# simpleshield.net
KiCad netlist of a schematic drawn in EAGLE
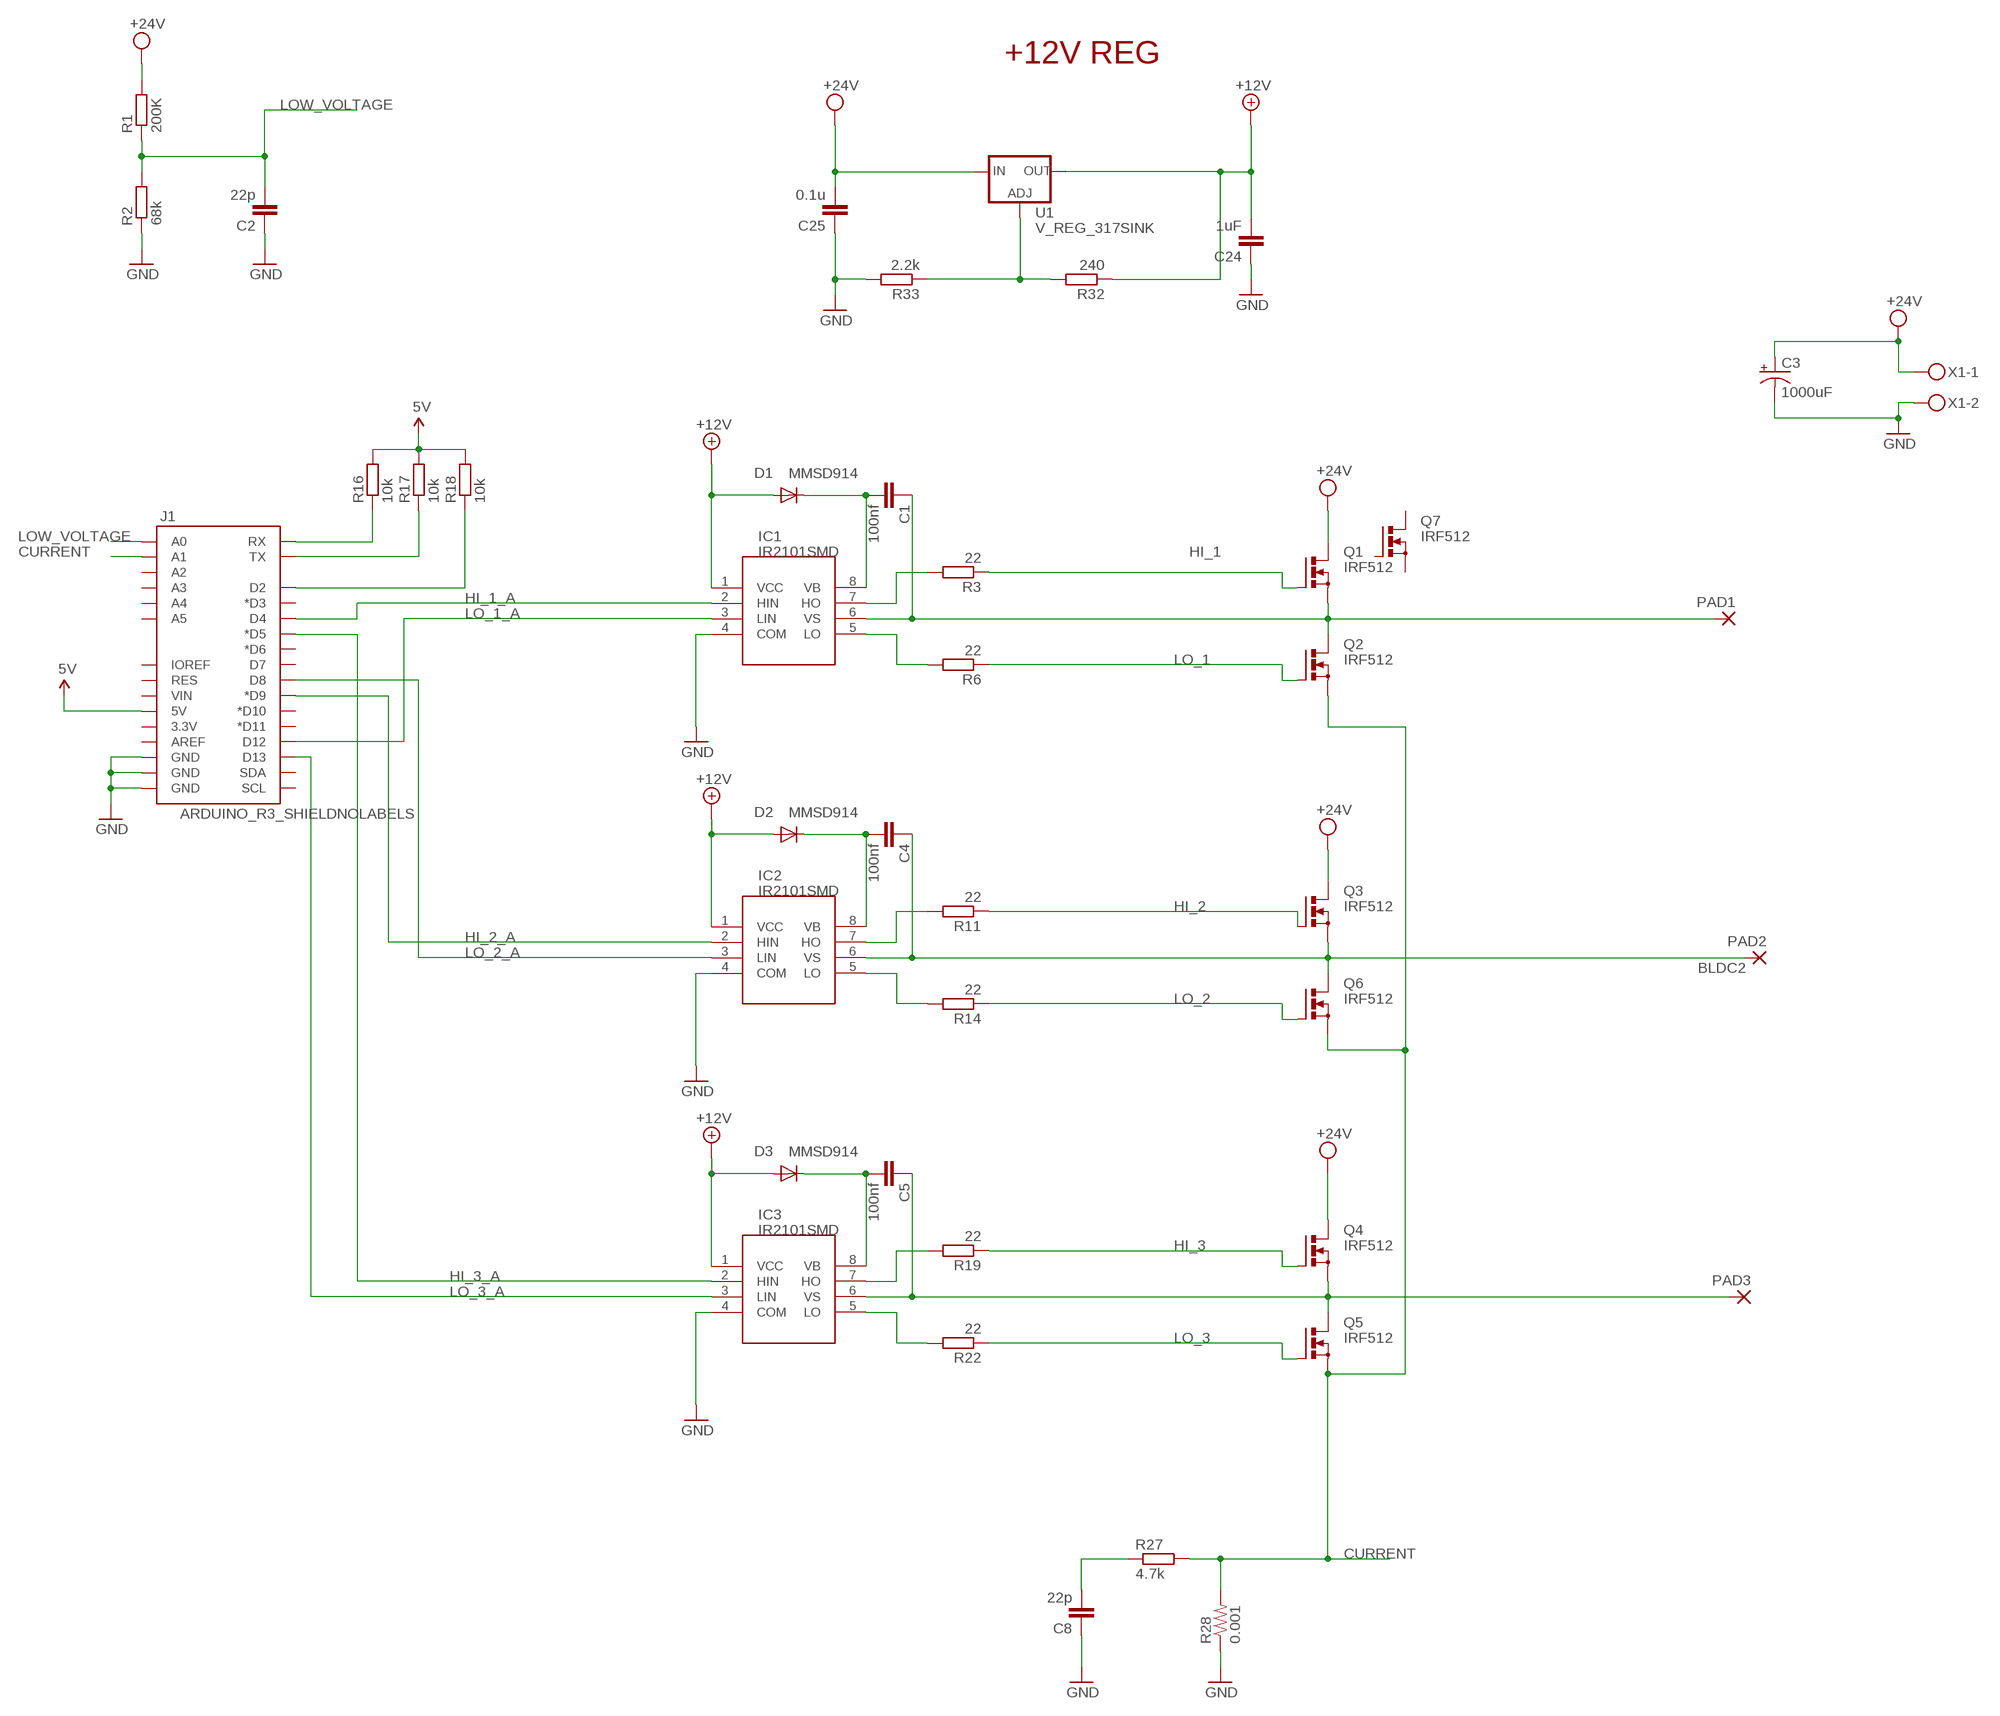
[diagram p0: schematic, sheet 1]

(export (version "E")
  (design (tool "Eeschema 10.0.6"))
  (components
    (comp (ref "C1")
      (value "100nf")
      (footprint "eagle-import:C1206")
      (libsource (lib "eagle-import") (part "C-EUC1206"))
    )
    (comp (ref "C2")
      (value "22p")
      (footprint "eagle-import:C1206")
      (libsource (lib "eagle-import") (part "C-EUC1206"))
    )
    (comp (ref "C3")
      (value "1000uF")
      (footprint "eagle-import:CPOL-RADIAL-1000UF-63V")
      (libsource (lib "eagle-import") (part "CAP_POLPTH3"))
    )
    (comp (ref "C4")
      (value "100nf")
      (footprint "eagle-import:C1206")
      (libsource (lib "eagle-import") (part "C-EUC1206"))
    )
    (comp (ref "C5")
      (value "100nf")
      (footprint "eagle-import:C1206")
      (libsource (lib "eagle-import") (part "C-EUC1206"))
    )
    (comp (ref "C8")
      (value "22p")
      (footprint "eagle-import:C1206")
      (libsource (lib "eagle-import") (part "C-EUC1206"))
    )
    (comp (ref "C24")
      (value "1uF")
      (footprint "eagle-import:C1206")
      (libsource (lib "eagle-import") (part "C-EUC1206"))
    )
    (comp (ref "C25")
      (value "0.1u")
      (footprint "eagle-import:C1206")
      (libsource (lib "eagle-import") (part "C-EUC1206"))
    )
    (comp (ref "D1")
      (value "MMSD914")
      (footprint "eagle-import:SOD123")
      (libsource (lib "eagle-import") (part "DIODE-SOD123"))
    )
    (comp (ref "D2")
      (value "MMSD914")
      (footprint "eagle-import:SOD123")
      (libsource (lib "eagle-import") (part "DIODE-SOD123"))
    )
    (comp (ref "D3")
      (value "MMSD914")
      (footprint "eagle-import:SOD123")
      (libsource (lib "eagle-import") (part "DIODE-SOD123"))
    )
    (comp (ref "IC1")
      (value "IR2101SMD")
      (footprint "eagle-import:SO08")
      (libsource (lib "eagle-import") (part "IR2101SMD"))
    )
    (comp (ref "IC2")
      (value "IR2101SMD")
      (footprint "eagle-import:SO08")
      (libsource (lib "eagle-import") (part "IR2101SMD"))
    )
    (comp (ref "IC3")
      (value "IR2101SMD")
      (footprint "eagle-import:SO08")
      (libsource (lib "eagle-import") (part "IR2101SMD"))
    )
    (comp (ref "J1")
      (value "ARDUINO_R3_SHIELDNOLABELS")
      (footprint "eagle-import:UNO_R3_SHIELD_NOLABELS")
      (libsource (lib "eagle-import") (part "ARDUINO_R3_SHIELDNOLABELS"))
    )
    (comp (ref "PAD1")
      (value "3,81/1,4")
      (footprint "eagle-import:3,81_1,4")
      (libsource (lib "eagle-import") (part "3,81/1,4"))
    )
    (comp (ref "PAD2")
      (value "3,81/1,4")
      (footprint "eagle-import:3,81_1,4")
      (libsource (lib "eagle-import") (part "3,81/1,4"))
    )
    (comp (ref "PAD3")
      (value "3,81/1,4")
      (footprint "eagle-import:3,81_1,4")
      (libsource (lib "eagle-import") (part "3,81/1,4"))
    )
    (comp (ref "Q1")
      (value "IRF512")
      (footprint "eagle-import:TO220BV")
      (libsource (lib "eagle-import") (part "IRF512"))
    )
    (comp (ref "Q2")
      (value "IRF512")
      (footprint "eagle-import:TO220BV")
      (libsource (lib "eagle-import") (part "IRF512"))
    )
    (comp (ref "Q3")
      (value "IRF512")
      (footprint "eagle-import:TO220BV")
      (libsource (lib "eagle-import") (part "IRF512"))
    )
    (comp (ref "Q4")
      (value "IRF512")
      (footprint "eagle-import:TO220BV")
      (libsource (lib "eagle-import") (part "IRF512"))
    )
    (comp (ref "Q5")
      (value "IRF512")
      (footprint "eagle-import:TO220BV")
      (libsource (lib "eagle-import") (part "IRF512"))
    )
    (comp (ref "Q6")
      (value "IRF512")
      (footprint "eagle-import:TO220BV")
      (libsource (lib "eagle-import") (part "IRF512"))
    )
    (comp (ref "Q7")
      (value "IRF512")
      (footprint "eagle-import:TO220BV")
      (libsource (lib "eagle-import") (part "IRF512"))
    )
    (comp (ref "R1")
      (value "200K")
      (footprint "eagle-import:R1206")
      (libsource (lib "eagle-import") (part "R-EU_R1206"))
    )
    (comp (ref "R2")
      (value "68k")
      (footprint "eagle-import:R1206")
      (libsource (lib "eagle-import") (part "R-EU_R1206"))
    )
    (comp (ref "R3")
      (value "22")
      (footprint "eagle-import:R1206")
      (libsource (lib "eagle-import") (part "R-EU_R1206"))
    )
    (comp (ref "R6")
      (value "22")
      (footprint "eagle-import:R1206")
      (libsource (lib "eagle-import") (part "R-EU_R1206"))
    )
    (comp (ref "R11")
      (value "22")
      (footprint "eagle-import:R1206")
      (libsource (lib "eagle-import") (part "R-EU_R1206"))
    )
    (comp (ref "R14")
      (value "22")
      (footprint "eagle-import:R1206")
      (libsource (lib "eagle-import") (part "R-EU_R1206"))
    )
    (comp (ref "R16")
      (value "10k")
      (footprint "eagle-import:R1206")
      (libsource (lib "eagle-import") (part "R-EU_R1206"))
    )
    (comp (ref "R17")
      (value "10k")
      (footprint "eagle-import:R1206")
      (libsource (lib "eagle-import") (part "R-EU_R1206"))
    )
    (comp (ref "R18")
      (value "10k")
      (footprint "eagle-import:R1206")
      (libsource (lib "eagle-import") (part "R-EU_R1206"))
    )
    (comp (ref "R19")
      (value "22")
      (footprint "eagle-import:R1206")
      (libsource (lib "eagle-import") (part "R-EU_R1206"))
    )
    (comp (ref "R22")
      (value "22")
      (footprint "eagle-import:R1206")
      (libsource (lib "eagle-import") (part "R-EU_R1206"))
    )
    (comp (ref "R27")
      (value "4.7k")
      (footprint "eagle-import:R1206")
      (libsource (lib "eagle-import") (part "R-EU_R1206"))
    )
    (comp (ref "R28")
      (value "0.001")
      (footprint "eagle-import:R2512")
      (libsource (lib "eagle-import") (part "R-US_R2512"))
    )
    (comp (ref "R32")
      (value "240")
      (footprint "eagle-import:R1206")
      (libsource (lib "eagle-import") (part "R-EU_R1206"))
    )
    (comp (ref "R33")
      (value "2.2k")
      (footprint "eagle-import:R1206")
      (libsource (lib "eagle-import") (part "R-EU_R1206"))
    )
    (comp (ref "U1")
      (value "V_REG_317SINK")
      (footprint "eagle-import:TO220-ADJ")
      (libsource (lib "eagle-import") (part "V_REG_317SINK"))
    )
    (comp (ref "X1")
      (value "MKDSN1,5/2-5,08")
      (footprint "eagle-import:MKDSN1,5_2-5,08")
      (fields (field (name "MPN") "MKDSN 1,5/2-5.08"))
      (libsource (lib "eagle-import") (part "MKDSN1,5/2-5,08"))
    )
  )
  (nets
    (net (code "1") (name "+12V") (class "Default")
      (node (ref "C24") (pin "2") (pinfunction "2_2") (pintype "passive"))
      (node (ref "D1") (pin "A") (pinfunction "A_A") (pintype "passive"))
      (node (ref "D2") (pin "A") (pinfunction "A_A") (pintype "passive"))
      (node (ref "D3") (pin "A") (pinfunction "A_A") (pintype "passive"))
      (node (ref "IC1") (pin "1") (pinfunction "VCC_1") (pintype "bidirectional"))
      (node (ref "IC2") (pin "1") (pinfunction "VCC_1") (pintype "bidirectional"))
      (node (ref "IC3") (pin "1") (pinfunction "VCC_1") (pintype "bidirectional"))
      (node (ref "R32") (pin "1") (pinfunction "1_1") (pintype "passive"))
      (node (ref "U1") (pin "OUT") (pinfunction "OUT_OUT") (pintype "output"))
    )
    (net (code "2") (name "+24V") (class "Default")
      (node (ref "C25") (pin "2") (pinfunction "2_2") (pintype "passive"))
      (node (ref "C3") (pin "1") (pinfunction "+_1") (pintype "passive"))
      (node (ref "Q1") (pin "D") (pinfunction "D_D") (pintype "passive"))
      (node (ref "Q3") (pin "D") (pinfunction "D_D") (pintype "passive"))
      (node (ref "Q4") (pin "D") (pinfunction "D_D") (pintype "passive"))
      (node (ref "R1") (pin "2") (pinfunction "2_2") (pintype "passive"))
      (node (ref "U1") (pin "IN") (pinfunction "IN_IN") (pintype "input"))
      (node (ref "X1") (pin "1") (pinfunction "KL_1") (pintype "passive"))
    )
    (net (code "3") (name "/BLDC2") (class "Default")
      (node (ref "C4") (pin "1") (pinfunction "1_1") (pintype "passive"))
      (node (ref "IC2") (pin "6") (pinfunction "VS_6") (pintype "bidirectional"))
      (node (ref "PAD2") (pin "1") (pinfunction "P_1") (pintype "passive"))
      (node (ref "Q3") (pin "S") (pinfunction "S_S") (pintype "passive"))
      (node (ref "Q6") (pin "D") (pinfunction "D_D") (pintype "passive"))
    )
    (net (code "4") (name "/CURRENT") (class "Default")
      (node (ref "J1") (pin "A1") (pinfunction "A1_A1") (pintype "bidirectional"))
      (node (ref "Q2") (pin "S") (pinfunction "S_S") (pintype "passive"))
      (node (ref "Q5") (pin "S") (pinfunction "S_S") (pintype "passive"))
      (node (ref "Q6") (pin "S") (pinfunction "S_S") (pintype "passive"))
      (node (ref "R27") (pin "2") (pinfunction "2_2") (pintype "passive"))
      (node (ref "R28") (pin "2") (pinfunction "2_2") (pintype "passive"))
    )
    (net (code "5") (name "/HI_1") (class "Default")
      (node (ref "Q1") (pin "G") (pinfunction "G_G") (pintype "passive"))
      (node (ref "R3") (pin "1") (pinfunction "1_1") (pintype "passive"))
    )
    (net (code "6") (name "/HI_1_A") (class "Default")
      (node (ref "IC1") (pin "2") (pinfunction "HIN_2") (pintype "bidirectional"))
      (node (ref "J1") (pin "D4") (pinfunction "D4_D4") (pintype "bidirectional"))
    )
    (net (code "7") (name "/HI_2") (class "Default")
      (node (ref "Q3") (pin "G") (pinfunction "G_G") (pintype "passive"))
      (node (ref "R11") (pin "1") (pinfunction "1_1") (pintype "passive"))
    )
    (net (code "8") (name "/HI_2_A") (class "Default")
      (node (ref "IC2") (pin "2") (pinfunction "HIN_2") (pintype "bidirectional"))
      (node (ref "J1") (pin "D9") (pinfunction "*D9_D9") (pintype "bidirectional"))
    )
    (net (code "9") (name "/HI_3") (class "Default")
      (node (ref "Q4") (pin "G") (pinfunction "G_G") (pintype "passive"))
      (node (ref "R19") (pin "1") (pinfunction "1_1") (pintype "passive"))
    )
    (net (code "10") (name "/HI_3_A") (class "Default")
      (node (ref "IC3") (pin "2") (pinfunction "HIN_2") (pintype "bidirectional"))
      (node (ref "J1") (pin "D5") (pinfunction "*D5_D5") (pintype "bidirectional"))
    )
    (net (code "11") (name "/LOW_VOLTAGE") (class "Default")
      (node (ref "C2") (pin "2") (pinfunction "2_2") (pintype "passive"))
      (node (ref "J1") (pin "A0") (pinfunction "A0_A0") (pintype "bidirectional"))
      (node (ref "R1") (pin "1") (pinfunction "1_1") (pintype "passive"))
      (node (ref "R2") (pin "2") (pinfunction "2_2") (pintype "passive"))
    )
    (net (code "12") (name "/LO_1") (class "Default")
      (node (ref "Q2") (pin "G") (pinfunction "G_G") (pintype "passive"))
      (node (ref "R6") (pin "1") (pinfunction "1_1") (pintype "passive"))
    )
    (net (code "13") (name "/LO_1_A") (class "Default")
      (node (ref "IC1") (pin "3") (pinfunction "LIN_3") (pintype "bidirectional"))
      (node (ref "J1") (pin "D12") (pinfunction "D12_D12") (pintype "bidirectional"))
    )
    (net (code "14") (name "/LO_2") (class "Default")
      (node (ref "Q6") (pin "G") (pinfunction "G_G") (pintype "passive"))
      (node (ref "R14") (pin "1") (pinfunction "1_1") (pintype "passive"))
    )
    (net (code "15") (name "/LO_2_A") (class "Default")
      (node (ref "IC2") (pin "3") (pinfunction "LIN_3") (pintype "bidirectional"))
      (node (ref "J1") (pin "D8") (pinfunction "D8_D8") (pintype "bidirectional"))
    )
    (net (code "16") (name "/LO_3") (class "Default")
      (node (ref "Q5") (pin "G") (pinfunction "G_G") (pintype "passive"))
      (node (ref "R22") (pin "1") (pinfunction "1_1") (pintype "passive"))
    )
    (net (code "17") (name "/LO_3_A") (class "Default")
      (node (ref "IC3") (pin "3") (pinfunction "LIN_3") (pintype "bidirectional"))
      (node (ref "J1") (pin "D13") (pinfunction "D13_D13") (pintype "bidirectional"))
    )
    (net (code "18") (name "5V") (class "Default")
      (node (ref "J1") (pin "5V") (pinfunction "5V_5V") (pintype "bidirectional"))
      (node (ref "R16") (pin "2") (pinfunction "2_2") (pintype "passive"))
      (node (ref "R17") (pin "2") (pinfunction "2_2") (pintype "passive"))
      (node (ref "R18") (pin "2") (pinfunction "2_2") (pintype "passive"))
    )
    (net (code "19") (name "GND") (class "Default")
      (node (ref "C2") (pin "1") (pinfunction "1_1") (pintype "passive"))
      (node (ref "C24") (pin "1") (pinfunction "1_1") (pintype "passive"))
      (node (ref "C25") (pin "1") (pinfunction "1_1") (pintype "passive"))
      (node (ref "C3") (pin "2") (pinfunction "-_2") (pintype "passive"))
      (node (ref "C8") (pin "1") (pinfunction "1_1") (pintype "passive"))
      (node (ref "IC1") (pin "4") (pinfunction "COM_4") (pintype "bidirectional"))
      (node (ref "IC2") (pin "4") (pinfunction "COM_4") (pintype "bidirectional"))
      (node (ref "IC3") (pin "4") (pinfunction "COM_4") (pintype "bidirectional"))
      (node (ref "J1") (pin "GND@0") (pinfunction "GND_GND@0") (pintype "bidirectional"))
      (node (ref "J1") (pin "GND@1") (pinfunction "GND_GND@1") (pintype "bidirectional"))
      (node (ref "J1") (pin "GND@2") (pinfunction "GND_GND@2") (pintype "bidirectional"))
      (node (ref "R2") (pin "1") (pinfunction "1_1") (pintype "passive"))
      (node (ref "R28") (pin "1") (pinfunction "1_1") (pintype "passive"))
      (node (ref "R33") (pin "2") (pinfunction "2_2") (pintype "passive"))
      (node (ref "X1") (pin "2") (pinfunction "KL_2") (pintype "passive"))
    )
    (net (code "20") (name "Net-(C8-Pad2)") (class "Default")
      (node (ref "C8") (pin "2") (pinfunction "2_2") (pintype "passive"))
      (node (ref "R27") (pin "1") (pinfunction "1_1") (pintype "passive"))
    )
    (net (code "21") (name "Net-(IC1-HO)") (class "Default")
      (node (ref "IC1") (pin "7") (pinfunction "HO_7") (pintype "bidirectional"))
      (node (ref "R3") (pin "2") (pinfunction "2_2") (pintype "passive"))
    )
    (net (code "22") (name "Net-(IC1-LO)") (class "Default")
      (node (ref "IC1") (pin "5") (pinfunction "LO_5") (pintype "bidirectional"))
      (node (ref "R6") (pin "2") (pinfunction "2_2") (pintype "passive"))
    )
    (net (code "23") (name "Net-(IC1-VB)") (class "Default")
      (node (ref "C1") (pin "2") (pinfunction "2_2") (pintype "passive"))
      (node (ref "D1") (pin "C") (pinfunction "C_C") (pintype "passive"))
      (node (ref "IC1") (pin "8") (pinfunction "VB_8") (pintype "bidirectional"))
    )
    (net (code "24") (name "Net-(IC1-VS)") (class "Default")
      (node (ref "C1") (pin "1") (pinfunction "1_1") (pintype "passive"))
      (node (ref "IC1") (pin "6") (pinfunction "VS_6") (pintype "bidirectional"))
      (node (ref "PAD1") (pin "1") (pinfunction "P_1") (pintype "passive"))
      (node (ref "Q1") (pin "S") (pinfunction "S_S") (pintype "passive"))
      (node (ref "Q2") (pin "D") (pinfunction "D_D") (pintype "passive"))
    )
    (net (code "25") (name "Net-(IC2-HO)") (class "Default")
      (node (ref "IC2") (pin "7") (pinfunction "HO_7") (pintype "bidirectional"))
      (node (ref "R11") (pin "2") (pinfunction "2_2") (pintype "passive"))
    )
    (net (code "26") (name "Net-(IC2-LO)") (class "Default")
      (node (ref "IC2") (pin "5") (pinfunction "LO_5") (pintype "bidirectional"))
      (node (ref "R14") (pin "2") (pinfunction "2_2") (pintype "passive"))
    )
    (net (code "27") (name "Net-(IC2-VB)") (class "Default")
      (node (ref "C4") (pin "2") (pinfunction "2_2") (pintype "passive"))
      (node (ref "D2") (pin "C") (pinfunction "C_C") (pintype "passive"))
      (node (ref "IC2") (pin "8") (pinfunction "VB_8") (pintype "bidirectional"))
    )
    (net (code "28") (name "Net-(IC3-HO)") (class "Default")
      (node (ref "IC3") (pin "7") (pinfunction "HO_7") (pintype "bidirectional"))
      (node (ref "R19") (pin "2") (pinfunction "2_2") (pintype "passive"))
    )
    (net (code "29") (name "Net-(IC3-LO)") (class "Default")
      (node (ref "IC3") (pin "5") (pinfunction "LO_5") (pintype "bidirectional"))
      (node (ref "R22") (pin "2") (pinfunction "2_2") (pintype "passive"))
    )
    (net (code "30") (name "Net-(IC3-VB)") (class "Default")
      (node (ref "C5") (pin "2") (pinfunction "2_2") (pintype "passive"))
      (node (ref "D3") (pin "C") (pinfunction "C_C") (pintype "passive"))
      (node (ref "IC3") (pin "8") (pinfunction "VB_8") (pintype "bidirectional"))
    )
    (net (code "31") (name "Net-(IC3-VS)") (class "Default")
      (node (ref "C5") (pin "1") (pinfunction "1_1") (pintype "passive"))
      (node (ref "IC3") (pin "6") (pinfunction "VS_6") (pintype "bidirectional"))
      (node (ref "PAD3") (pin "1") (pinfunction "P_1") (pintype "passive"))
      (node (ref "Q4") (pin "S") (pinfunction "S_S") (pintype "passive"))
      (node (ref "Q5") (pin "D") (pinfunction "D_D") (pintype "passive"))
    )
    (net (code "32") (name "Net-(J1-PadD2)") (class "Default")
      (node (ref "J1") (pin "D2") (pinfunction "D2_D2") (pintype "bidirectional"))
      (node (ref "R18") (pin "1") (pinfunction "1_1") (pintype "passive"))
    )
    (net (code "33") (name "Net-(J1-PadRX)") (class "Default")
      (node (ref "J1") (pin "RX") (pinfunction "RX_RX") (pintype "bidirectional"))
      (node (ref "R16") (pin "1") (pinfunction "1_1") (pintype "passive"))
    )
    (net (code "34") (name "Net-(J1-PadTX)") (class "Default")
      (node (ref "J1") (pin "TX") (pinfunction "TX_TX") (pintype "bidirectional"))
      (node (ref "R17") (pin "1") (pinfunction "1_1") (pintype "passive"))
    )
    (net (code "35") (name "Net-(R32-Pad2)") (class "Default")
      (node (ref "R32") (pin "2") (pinfunction "2_2") (pintype "passive"))
      (node (ref "R33") (pin "1") (pinfunction "1_1") (pintype "passive"))
      (node (ref "U1") (pin "ADJ") (pinfunction "ADJ_ADJ") (pintype "input"))
    )
    (net (code "36") (name "unconnected-(J1-*D3-PadD3)") (class "Default")
      (node (ref "J1") (pin "D3") (pinfunction "*D3_D3") (pintype "bidirectional"))
    )
    (net (code "37") (name "unconnected-(J1-*D6-PadD6)") (class "Default")
      (node (ref "J1") (pin "D6") (pinfunction "*D6_D6") (pintype "bidirectional"))
    )
    (net (code "38") (name "unconnected-(J1-*D10-PadD10)") (class "Default")
      (node (ref "J1") (pin "D10") (pinfunction "*D10_D10") (pintype "bidirectional"))
    )
    (net (code "39") (name "unconnected-(J1-*D11-PadD11)") (class "Default")
      (node (ref "J1") (pin "D11") (pinfunction "*D11_D11") (pintype "bidirectional"))
    )
    (net (code "40") (name "unconnected-(J1-Pad3.3V)") (class "Default")
      (node (ref "J1") (pin "3.3V") (pinfunction "3.3V_3.3V") (pintype "bidirectional"))
    )
    (net (code "41") (name "unconnected-(J1-PadA2)") (class "Default")
      (node (ref "J1") (pin "A2") (pinfunction "A2_A2") (pintype "bidirectional"))
    )
    (net (code "42") (name "unconnected-(J1-PadA3)") (class "Default")
      (node (ref "J1") (pin "A3") (pinfunction "A3_A3") (pintype "bidirectional"))
    )
    (net (code "43") (name "unconnected-(J1-PadA4)") (class "Default")
      (node (ref "J1") (pin "A4") (pinfunction "A4_A4") (pintype "bidirectional"))
    )
    (net (code "44") (name "unconnected-(J1-PadA5)") (class "Default")
      (node (ref "J1") (pin "A5") (pinfunction "A5_A5") (pintype "bidirectional"))
    )
    (net (code "45") (name "unconnected-(J1-PadAREF)") (class "Default")
      (node (ref "J1") (pin "AREF") (pinfunction "AREF_AREF") (pintype "bidirectional"))
    )
    (net (code "46") (name "unconnected-(J1-PadD7)") (class "Default")
      (node (ref "J1") (pin "D7") (pinfunction "D7_D7") (pintype "bidirectional"))
    )
    (net (code "47") (name "unconnected-(J1-PadIOREF)") (class "Default")
      (node (ref "J1") (pin "IOREF") (pinfunction "IOREF_IOREF") (pintype "bidirectional"))
    )
    (net (code "48") (name "unconnected-(J1-PadRES)") (class "Default")
      (node (ref "J1") (pin "RES") (pinfunction "RES_RES") (pintype "bidirectional"))
    )
    (net (code "49") (name "unconnected-(J1-PadSCL)") (class "Default")
      (node (ref "J1") (pin "SCL") (pinfunction "SCL_SCL") (pintype "bidirectional"))
    )
    (net (code "50") (name "unconnected-(J1-PadSDA)") (class "Default")
      (node (ref "J1") (pin "SDA") (pinfunction "SDA_SDA") (pintype "bidirectional"))
    )
    (net (code "51") (name "unconnected-(J1-PadVIN)") (class "Default")
      (node (ref "J1") (pin "VIN") (pinfunction "VIN_VIN") (pintype "bidirectional"))
    )
    (net (code "52") (name "unconnected-(Q7-PadD)") (class "Default")
      (node (ref "Q7") (pin "D") (pinfunction "D_D") (pintype "passive"))
    )
    (net (code "53") (name "unconnected-(Q7-PadG)") (class "Default")
      (node (ref "Q7") (pin "G") (pinfunction "G_G") (pintype "passive"))
    )
    (net (code "54") (name "unconnected-(Q7-PadS)") (class "Default")
      (node (ref "Q7") (pin "S") (pinfunction "S_S") (pintype "passive"))
    )
  )
)
